# COM-CDH.net
KiCad netlist of a schematic drawn in Altium Designer
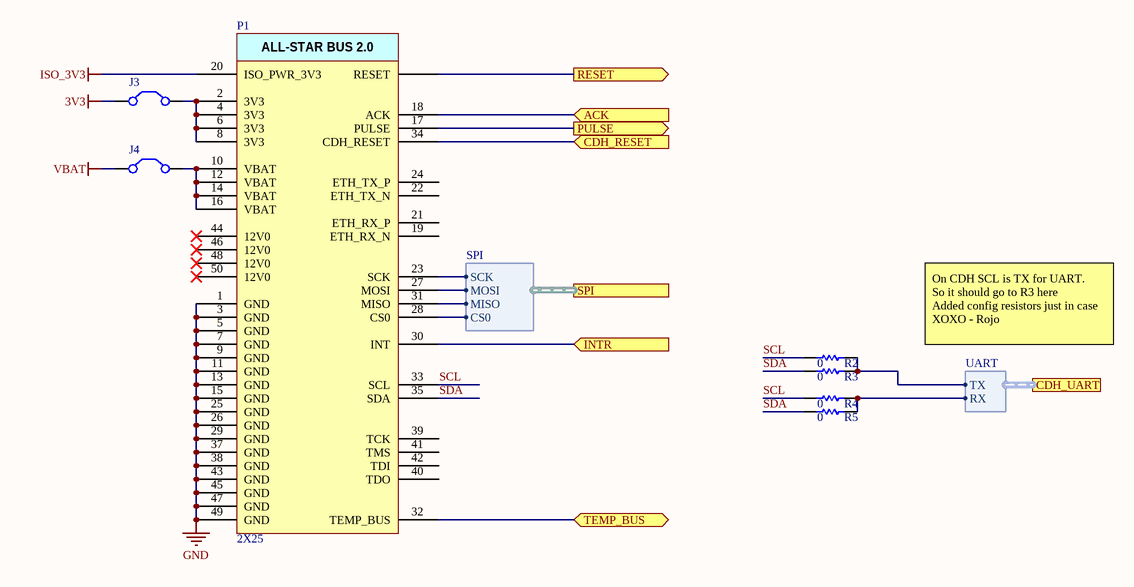
[diagram p0: COM-CDH.SchDoc]

(export (version "E")
  (design (tool "Eeschema 10.0.6"))
  (components
    (comp (ref "J3")
      (value "Jumper")
      (footprint "C1206")
      (description "Jumper Wire")
      (fields (field (name "PUBLISHER") "Altium Limited"))
      (libsource (lib "Miscellaneous Devices") (part "Jumper"))
    )
    (comp (ref "J4")
      (value "Jumper")
      (footprint "C1206")
      (description "Jumper Wire")
      (fields (field (name "PUBLISHER") "Altium Limited"))
      (libsource (lib "Miscellaneous Devices") (part "Jumper"))
    )
    (comp (ref "P1")
      (value "2X25")
      (footprint "LS2-125-01-X-D-RA1")
      (description "2.00 mm Locking Hermaphroditic Terminal/Socke")
      (fields (field (name "PARTNUMBER") "LS2-125-01-X-D-RA1") (field (name "MANUFACTURER") "Samtec"))
      (libsource (lib "PolarCube") (part "LS2-125"))
    )
    (comp (ref "R2")
      (value "CRCW06030000Z0EAC")
      (footprint "1608[0603]")
      (description "RES SMD 0 OHM JUMP 1/10W 0603")
      (fields
        (field (name "RESISTANCE") "0")
        (field (name "PARTNUMBER") "CRCW06030000Z0EA")
        (field (name "MANUFACTURER") "Vishay")
      )
      (libsource (lib "PolarCube") (part "Res"))
    )
    (comp (ref "R3")
      (value "CRCW06030000Z0EAC")
      (footprint "1608[0603]")
      (description "RES SMD 0 OHM JUMP 1/10W 0603")
      (fields
        (field (name "RESISTANCE") "0")
        (field (name "PARTNUMBER") "CRCW06030000Z0EA")
        (field (name "MANUFACTURER") "Vishay")
      )
      (libsource (lib "PolarCube") (part "Res"))
    )
    (comp (ref "R4")
      (value "CRCW06030000Z0EAC")
      (footprint "1608[0603]")
      (description "RES SMD 0 OHM JUMP 1/10W 0603")
      (fields
        (field (name "RESISTANCE") "0")
        (field (name "PARTNUMBER") "CRCW06030000Z0EA")
        (field (name "MANUFACTURER") "Vishay")
      )
      (libsource (lib "PolarCube") (part "Res"))
    )
    (comp (ref "R5")
      (value "CRCW06030000Z0EAC")
      (footprint "1608[0603]")
      (description "RES SMD 0 OHM JUMP 1/10W 0603")
      (fields
        (field (name "RESISTANCE") "0")
        (field (name "PARTNUMBER") "CRCW06030000Z0EA")
        (field (name "MANUFACTURER") "Vishay")
      )
      (libsource (lib "PolarCube") (part "Res"))
    )
  )
  (nets
    (net (code "3") (name "/ACK") (class "Default")
      (node (ref "P1") (pin "18") (pinfunction "ACK_18") (pintype "passive"))
    )
    (net (code "4") (name "/CDH_RESET") (class "Default")
      (node (ref "P1") (pin "34") (pinfunction "CDH_RESET_34") (pintype "passive"))
    )
    (net (code "5") (name "/CS0") (class "Default")
      (node (ref "P1") (pin "28") (pinfunction "CS0_28") (pintype "passive"))
    )
    (net (code "6") (name "/INTR") (class "Default")
      (node (ref "P1") (pin "30") (pinfunction "INT_30") (pintype "passive"))
    )
    (net (code "7") (name "/MISO") (class "Default")
      (node (ref "P1") (pin "31") (pinfunction "MISO_31") (pintype "passive"))
    )
    (net (code "8") (name "/MOSI") (class "Default")
      (node (ref "P1") (pin "27") (pinfunction "MOSI_27") (pintype "passive"))
    )
    (net (code "9") (name "/PULSE") (class "Default")
      (node (ref "P1") (pin "17") (pinfunction "PULSE_17") (pintype "passive"))
    )
    (net (code "10") (name "/RESET") (class "Default")
      (node (ref "P1") (pin "36") (pinfunction "RESET_36") (pintype "passive"))
    )
    (net (code "11") (name "/RX") (class "Default")
      (node (ref "R4") (pin "2") (pinfunction "2_2") (pintype "passive"))
      (node (ref "R5") (pin "2") (pinfunction "2_2") (pintype "passive"))
    )
    (net (code "12") (name "/SCK") (class "Default")
      (node (ref "P1") (pin "23") (pinfunction "SCK_23") (pintype "passive"))
    )
    (net (code "13") (name "/SCL") (class "Default")
      (node (ref "P1") (pin "33") (pinfunction "SCL_33") (pintype "passive"))
      (node (ref "R2") (pin "1") (pinfunction "1_1") (pintype "passive"))
      (node (ref "R4") (pin "1") (pinfunction "1_1") (pintype "passive"))
    )
    (net (code "14") (name "/SDA") (class "Default")
      (node (ref "P1") (pin "35") (pinfunction "SDA_35") (pintype "passive"))
      (node (ref "R3") (pin "1") (pinfunction "1_1") (pintype "passive"))
      (node (ref "R5") (pin "1") (pinfunction "1_1") (pintype "passive"))
    )
    (net (code "15") (name "/TEMP_BUS") (class "Default")
      (node (ref "P1") (pin "32") (pinfunction "TEMP_BUS_32") (pintype "passive"))
    )
    (net (code "16") (name "/TX") (class "Default")
      (node (ref "R2") (pin "2") (pinfunction "2_2") (pintype "passive"))
      (node (ref "R3") (pin "2") (pinfunction "2_2") (pintype "passive"))
    )
    (net (code "19") (name "3V3") (class "Default")
      (node (ref "J3") (pin "1") (pinfunction "C1_1") (pintype "passive"))
    )
    (net (code "20") (name "GND") (class "Default")
      (node (ref "P1") (pin "1") (pinfunction "GND_1") (pintype "passive"))
      (node (ref "P1") (pin "11") (pinfunction "GND_11") (pintype "passive"))
      (node (ref "P1") (pin "13") (pinfunction "GND_13") (pintype "passive"))
      (node (ref "P1") (pin "15") (pinfunction "GND_15") (pintype "passive"))
      (node (ref "P1") (pin "25") (pinfunction "GND_25") (pintype "passive"))
      (node (ref "P1") (pin "26") (pinfunction "GND_26") (pintype "passive"))
      (node (ref "P1") (pin "29") (pinfunction "GND_29") (pintype "passive"))
      (node (ref "P1") (pin "3") (pinfunction "GND_3") (pintype "passive"))
      (node (ref "P1") (pin "37") (pinfunction "GND_37") (pintype "passive"))
      (node (ref "P1") (pin "38") (pinfunction "GND_38") (pintype "passive"))
      (node (ref "P1") (pin "43") (pinfunction "GND_43") (pintype "passive"))
      (node (ref "P1") (pin "45") (pinfunction "GND_45") (pintype "passive"))
      (node (ref "P1") (pin "47") (pinfunction "GND_47") (pintype "passive"))
      (node (ref "P1") (pin "49") (pinfunction "GND_49") (pintype "passive"))
      (node (ref "P1") (pin "5") (pinfunction "GND_5") (pintype "passive"))
      (node (ref "P1") (pin "7") (pinfunction "GND_7") (pintype "passive"))
      (node (ref "P1") (pin "9") (pinfunction "GND_9") (pintype "passive"))
    )
    (net (code "21") (name "ISO_3V3") (class "Default")
      (node (ref "P1") (pin "20") (pinfunction "ISO_PWR_3V3_20") (pintype "passive"))
    )
    (net (code "22") (name "Net-(J3-C2)") (class "Default")
      (node (ref "J3") (pin "2") (pinfunction "C2_2") (pintype "passive"))
      (node (ref "P1") (pin "2") (pinfunction "3V3_2") (pintype "passive"))
      (node (ref "P1") (pin "4") (pinfunction "3V3_4") (pintype "passive"))
      (node (ref "P1") (pin "6") (pinfunction "3V3_6") (pintype "passive"))
      (node (ref "P1") (pin "8") (pinfunction "3V3_8") (pintype "passive"))
    )
    (net (code "23") (name "Net-(J4-C2)") (class "Default")
      (node (ref "J4") (pin "2") (pinfunction "C2_2") (pintype "passive"))
      (node (ref "P1") (pin "10") (pinfunction "VBAT_10") (pintype "passive"))
      (node (ref "P1") (pin "12") (pinfunction "VBAT_12") (pintype "passive"))
      (node (ref "P1") (pin "14") (pinfunction "VBAT_14") (pintype "passive"))
      (node (ref "P1") (pin "16") (pinfunction "VBAT_16") (pintype "passive"))
    )
    (net (code "24") (name "VBAT") (class "Default")
      (node (ref "J4") (pin "1") (pinfunction "C1_1") (pintype "passive"))
    )
    (net (code "25") (name "unconnected-(P1-12V0-Pad44)") (class "Default")
      (node (ref "P1") (pin "44") (pinfunction "12V0_44") (pintype "passive+no_connect"))
    )
    (net (code "26") (name "unconnected-(P1-12V0-Pad46)") (class "Default")
      (node (ref "P1") (pin "46") (pinfunction "12V0_46") (pintype "passive+no_connect"))
    )
    (net (code "27") (name "unconnected-(P1-12V0-Pad48)") (class "Default")
      (node (ref "P1") (pin "48") (pinfunction "12V0_48") (pintype "passive+no_connect"))
    )
    (net (code "28") (name "unconnected-(P1-12V0-Pad50)") (class "Default")
      (node (ref "P1") (pin "50") (pinfunction "12V0_50") (pintype "passive+no_connect"))
    )
    (net (code "29") (name "unconnected-(P1-ETH_RX_N-Pad19)") (class "Default")
      (node (ref "P1") (pin "19") (pinfunction "ETH_RX_N_19") (pintype "passive"))
    )
    (net (code "30") (name "unconnected-(P1-ETH_RX_P-Pad21)") (class "Default")
      (node (ref "P1") (pin "21") (pinfunction "ETH_RX_P_21") (pintype "passive"))
    )
    (net (code "31") (name "unconnected-(P1-ETH_TX_N-Pad22)") (class "Default")
      (node (ref "P1") (pin "22") (pinfunction "ETH_TX_N_22") (pintype "passive"))
    )
    (net (code "32") (name "unconnected-(P1-ETH_TX_P-Pad24)") (class "Default")
      (node (ref "P1") (pin "24") (pinfunction "ETH_TX_P_24") (pintype "passive"))
    )
    (net (code "33") (name "unconnected-(P1-TCK-Pad39)") (class "Default")
      (node (ref "P1") (pin "39") (pinfunction "TCK_39") (pintype "passive"))
    )
    (net (code "34") (name "unconnected-(P1-TDI-Pad42)") (class "Default")
      (node (ref "P1") (pin "42") (pinfunction "TDI_42") (pintype "passive"))
    )
    (net (code "35") (name "unconnected-(P1-TDO-Pad40)") (class "Default")
      (node (ref "P1") (pin "40") (pinfunction "TDO_40") (pintype "passive"))
    )
    (net (code "36") (name "unconnected-(P1-TMS-Pad41)") (class "Default")
      (node (ref "P1") (pin "41") (pinfunction "TMS_41") (pintype "passive"))
    )
  )
)
